# Sheet1.net
KiCad netlist of a schematic drawn in Altium Designer
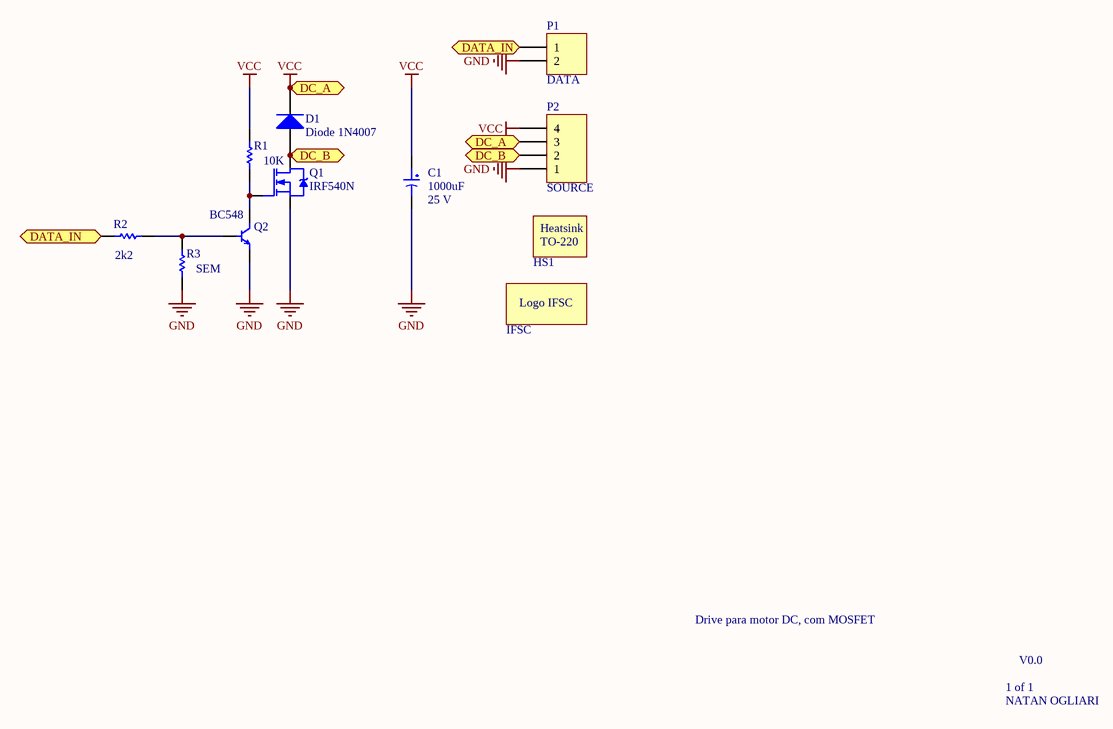
[diagram p0: Sheet1.SchDoc]

(export (version "E")
  (design (tool "Eeschema 10.0.6"))
  (components
    (comp (ref "C1")
      (value "1000uF")
      (footprint "CP-RAD-8.0mm-20.0mm-3.5mm")
      (description "Electrolytic Capacitor")
      (fields (field (name "VOLTAGE") "25 V"))
      (libsource (lib "GPDSE") (part "Capacitor-Electrolytic"))
    )
    (comp (ref "D1")
      (value "Diode 1N4007")
      (footprint "DO-41")
      (description "1 Amp General Purpose Rectifier")
      (fields (field (name "PUBLISHER") "Altium Limited"))
      (libsource (lib "Miscellaneous Devices") (part "Diode 1N4007"))
    )
    (comp (ref "HS1")
      (value "HS-TO-220")
      (footprint "HS-TO-220-180847")
      (description "Heatsink TO-220")
      (libsource (lib "GPDSE") (part "HS-TO-220"))
    )
    (comp (ref "P1")
      (value "DATA")
      (footprint "HDR1X2")
      (description "Header, 2-Pin")
      (fields (field (name "PUBLISHER") "Altium Limited"))
      (libsource (lib "Miscellaneous Connectors") (part "Header 2"))
    )
    (comp (ref "P2")
      (value "SOURCE")
      (footprint "KRE_4")
      (description "Terminal Block 1x4")
      (libsource (lib "GPDSE") (part "KRE_4"))
    )
    (comp (ref "Q1")
      (value "IRF540N")
      (footprint "TO-220/123")
      (description "HEXFET Power MOSFET")
      (libsource (lib "GPDSE") (part "IRFZ46N"))
    )
    (comp (ref "Q2")
      (value "BC548")
      (footprint "TO-92/CBE")
      (description "NPN Epitaxial Silicon Transistor")
      (fields (field (name "COMPLEMENTARY PART") "BC558"))
      (libsource (lib "GPDSE") (part "BC548"))
    )
    (comp (ref "R1")
      (value "10K")
      (footprint "AXIAL-0.5")
      (description "Semiconductor Resistor")
      (fields (field (name "Comment") "Res Semi") (field (name "PUBLISHER") "Altium Limited"))
      (libsource (lib "Miscellaneous Devices") (part "Res Semi"))
    )
    (comp (ref "R2")
      (value "2k2")
      (footprint "AXIAL-0.5")
      (description "Semiconductor Resistor")
      (fields (field (name "Comment") "Res Semi") (field (name "PUBLISHER") "Altium Limited"))
      (libsource (lib "Miscellaneous Devices") (part "Res Semi"))
    )
    (comp (ref "R3")
      (value "SEM")
      (footprint "AXIAL-0.5")
      (description "Semiconductor Resistor")
      (fields (field (name "Comment") "Res Semi") (field (name "PUBLISHER") "Altium Limited"))
      (libsource (lib "Miscellaneous Devices") (part "Res Semi"))
    )
    (comp (ref "X1")
      (value "IFSC")
      (footprint "IFSC_SILK")
      (description "Logomarca IFSC")
      (libsource (lib "GPDSE") (part "IFSC"))
    )
  )
  (nets
    (net (code "1") (name "/DATA_IN") (class "Default")
      (node (ref "P1") (pin "1") (pinfunction "1_1") (pintype "passive"))
      (node (ref "R2") (pin "1") (pinfunction "1_1") (pintype "passive"))
    )
    (net (code "2") (name "/DC_B") (class "Default")
      (node (ref "D1") (pin "1") (pinfunction "A_1") (pintype "passive"))
      (node (ref "P2") (pin "2") (pinfunction "2_2") (pintype "passive"))
      (node (ref "Q1") (pin "D") (pinfunction "D_D") (pintype "passive"))
    )
    (net (code "3") (name "GND") (class "Default")
      (node (ref "C1") (pin "2") (pinfunction "2_2") (pintype "passive"))
      (node (ref "P1") (pin "2") (pinfunction "2_2") (pintype "passive"))
      (node (ref "P2") (pin "1") (pinfunction "1_1") (pintype "passive"))
      (node (ref "Q1") (pin "S") (pinfunction "S_S") (pintype "passive"))
      (node (ref "Q2") (pin "E") (pinfunction "E_E") (pintype "passive"))
      (node (ref "R3") (pin "1") (pinfunction "1_1") (pintype "passive"))
    )
    (net (code "4") (name "Net-(Q1-PadG)") (class "Default")
      (node (ref "Q1") (pin "G") (pinfunction "G_G") (pintype "passive"))
      (node (ref "Q2") (pin "C") (pinfunction "C_C") (pintype "passive"))
      (node (ref "R1") (pin "1") (pinfunction "1_1") (pintype "passive"))
    )
    (net (code "5") (name "Net-(Q2-PadB)") (class "Default")
      (node (ref "Q2") (pin "B") (pinfunction "B_B") (pintype "passive"))
      (node (ref "R2") (pin "2") (pinfunction "2_2") (pintype "passive"))
      (node (ref "R3") (pin "2") (pinfunction "2_2") (pintype "passive"))
    )
    (net (code "6") (name "VCC") (class "Default")
      (node (ref "C1") (pin "1") (pinfunction "1_1") (pintype "passive"))
      (node (ref "D1") (pin "2") (pinfunction "K_2") (pintype "passive"))
      (node (ref "P2") (pin "3") (pinfunction "3_3") (pintype "passive"))
      (node (ref "P2") (pin "4") (pinfunction "4_4") (pintype "passive"))
      (node (ref "R1") (pin "2") (pinfunction "2_2") (pintype "passive"))
    )
  )
)
